# OptoBed.net
KiCad netlist of a schematic drawn in EAGLE
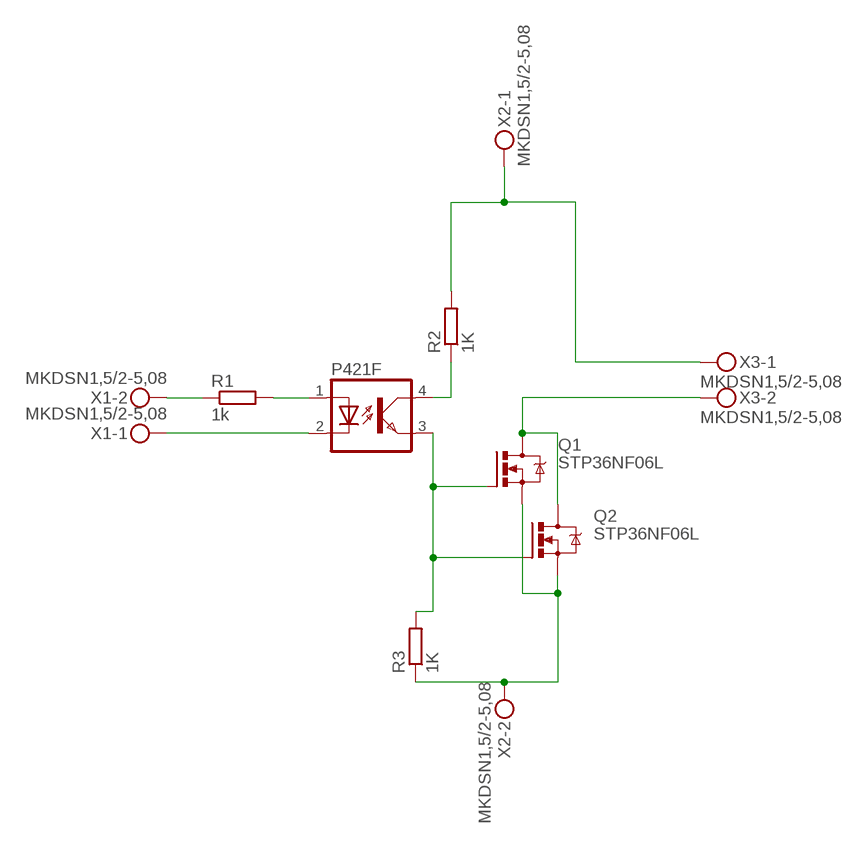
[diagram p0: schematic, sheet 1]

(export (version "E")
  (design (tool "Eeschema 10.0.6"))
  (components
    (comp (ref "P421F")
      (value "OPTOTRANSPC817")
      (footprint "eagle-import:DIL04")
      (fields (field (name "MPN") "PC817X4J000F"))
      (libsource (lib "eagle-import") (part "OPTOTRANSPC817"))
    )
    (comp (ref "Q1")
      (value "STP36NF06L")
      (footprint "eagle-import:TO220BV")
      (libsource (lib "eagle-import") (part "IRF740"))
    )
    (comp (ref "Q2")
      (value "STP36NF06L")
      (footprint "eagle-import:TO220BV")
      (libsource (lib "eagle-import") (part "IRF740"))
    )
    (comp (ref "R1")
      (value "1k")
      (footprint "eagle-import:R0805")
      (libsource (lib "eagle-import") (part "R_0805"))
    )
    (comp (ref "R2")
      (value "1K")
      (footprint "eagle-import:R0805")
      (libsource (lib "eagle-import") (part "R_0805"))
    )
    (comp (ref "R3")
      (value "1K")
      (footprint "eagle-import:R0805")
      (libsource (lib "eagle-import") (part "R_0805"))
    )
    (comp (ref "X1")
      (value "MKDSN1,5/2-5,08")
      (footprint "eagle-import:MKDSN1,5_2-5,08")
      (libsource (lib "eagle-import") (part "MKDSN1,5/2-5,08"))
    )
    (comp (ref "X2")
      (value "MKDSN1,5/2-5,08")
      (footprint "eagle-import:MKDSN1,5_2-5,08")
      (libsource (lib "eagle-import") (part "MKDSN1,5/2-5,08"))
    )
    (comp (ref "X3")
      (value "MKDSN1,5/2-5,08")
      (footprint "eagle-import:MKDSN1,5_2-5,08")
      (libsource (lib "eagle-import") (part "MKDSN1,5/2-5,08"))
    )
  )
  (nets
    (net (code "1") (name "Net-(P421F-A)") (class "Default")
      (node (ref "P421F") (pin "1") (pinfunction "A_1") (pintype "passive"))
      (node (ref "R1") (pin "2") (pinfunction "2_2") (pintype "passive"))
    )
    (net (code "2") (name "Net-(P421F-C)") (class "Default")
      (node (ref "P421F") (pin "2") (pinfunction "C_2") (pintype "passive"))
      (node (ref "X1") (pin "1") (pinfunction "KL_1") (pintype "passive"))
    )
    (net (code "3") (name "Net-(P421F-COL)") (class "Default")
      (node (ref "P421F") (pin "4") (pinfunction "COL_4") (pintype "passive"))
      (node (ref "R2") (pin "1") (pinfunction "1_1") (pintype "passive"))
    )
    (net (code "4") (name "Net-(P421F-EMIT)") (class "Default")
      (node (ref "P421F") (pin "3") (pinfunction "EMIT_3") (pintype "passive"))
      (node (ref "Q1") (pin "G") (pinfunction "G_G") (pintype "passive"))
      (node (ref "Q2") (pin "G") (pinfunction "G_G") (pintype "passive"))
      (node (ref "R3") (pin "2") (pinfunction "2_2") (pintype "passive"))
    )
    (net (code "5") (name "Net-(X1B-KL)") (class "Default")
      (node (ref "R1") (pin "1") (pinfunction "1_1") (pintype "passive"))
      (node (ref "X1") (pin "2") (pinfunction "KL_2") (pintype "passive"))
    )
    (net (code "6") (name "Net-(X2A-KL)") (class "Default")
      (node (ref "R2") (pin "2") (pinfunction "2_2") (pintype "passive"))
      (node (ref "X2") (pin "1") (pinfunction "KL_1") (pintype "passive"))
      (node (ref "X3") (pin "1") (pinfunction "KL_1") (pintype "passive"))
    )
    (net (code "7") (name "Net-(X2B-KL)") (class "Default")
      (node (ref "Q1") (pin "S") (pinfunction "S_S") (pintype "passive"))
      (node (ref "Q2") (pin "S") (pinfunction "S_S") (pintype "passive"))
      (node (ref "R3") (pin "1") (pinfunction "1_1") (pintype "passive"))
      (node (ref "X2") (pin "2") (pinfunction "KL_2") (pintype "passive"))
    )
    (net (code "8") (name "Net-(X3B-KL)") (class "Default")
      (node (ref "Q1") (pin "D") (pinfunction "D_D") (pintype "passive"))
      (node (ref "Q2") (pin "D") (pinfunction "D_D") (pintype "passive"))
      (node (ref "X3") (pin "2") (pinfunction "KL_2") (pintype "passive"))
    )
  )
)
